# So_do_nguyen_ly.net
KiCad netlist of a schematic drawn in Altium Designer
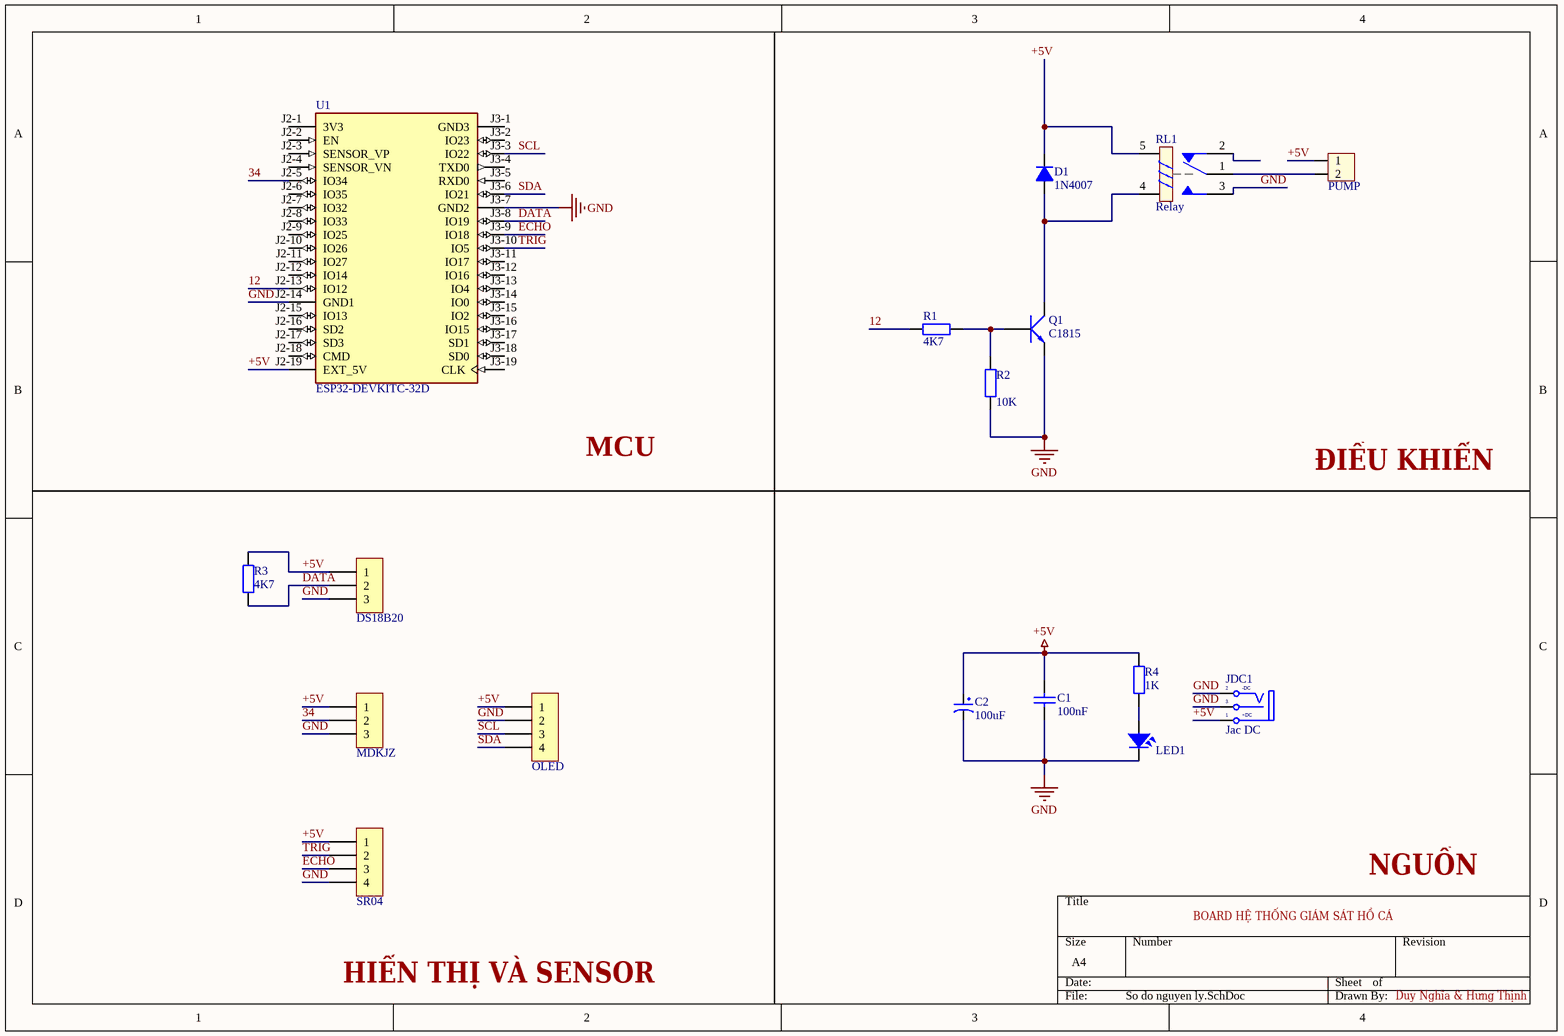
[diagram p0: So do nguyen ly.SchDoc]

(export (version "E")
  (design (tool "Eeschema 10.0.6"))
  (components
    (comp (ref "C1")
      (value "100nF")
      (footprint "tu gom")
      (description "Cắm")
      (libsource (lib "Altium_Lib_by_KhueNguyenCreator") (part "Tu gom 15pF 50V"))
    )
    (comp (ref "C2")
      (value "100uF")
      (footprint "tu hoa 5mm")
      (description "Cắm")
      (libsource (lib "Altium_Lib_by_KhueNguyenCreator") (part "Tu Hoa 100uF 16V 5x7"))
    )
    (comp (ref "D1")
      (value "1N4007")
      (footprint "D1A")
      (description "Diode 1A")
      (libsource (lib "syhaunguyen") (part "D1A"))
    )
    (comp (ref "H1")
      (value "PUMP")
      (footprint "XH2.54M-2")
      (description "Cắm")
      (libsource (lib "Altium_Lib_by_KhueNguyenCreator") (part "Header 2P 2.54 Duc Thang"))
    )
    (comp (ref "H2")
      (value "DS18B20")
      (footprint "Header 3P DC 2.54")
      (description "Cắm")
      (libsource (lib "Altium_Lib_by_KhueNguyenCreator") (part "Header 3P 2.54 Duc Cong"))
    )
    (comp (ref "H3")
      (value "MDKJZ")
      (footprint "Header 3P DC 2.54")
      (description "Cắm")
      (libsource (lib "Altium_Lib_by_KhueNguyenCreator") (part "Header 3P 2.54 Duc Cong"))
    )
    (comp (ref "H4")
      (value "OLED")
      (footprint "XH2.54M-4")
      (description "Cắm")
      (libsource (lib "Altium_Lib_by_KhueNguyenCreator") (part "Header 4P 2.54 Duc Thang"))
    )
    (comp (ref "H5")
      (value "SR04")
      (footprint "XH2.54M-4")
      (description "Cắm")
      (libsource (lib "Altium_Lib_by_KhueNguyenCreator") (part "Header 4P 2.54 Duc Thang"))
    )
    (comp (ref "JDC1")
      (value "Jac DC")
      (footprint "DC-IN")
      (description "Jac DC input")
      (libsource (lib "syhaunguyen") (part "DCIN"))
    )
    (comp (ref "LED1")
      (value "LED")
      (footprint "LED-3")
      (description "LED Single colour Green and Red")
      (libsource (lib "syhaunguyen") (part "LED"))
    )
    (comp (ref "Q1")
      (value "C1815")
      (footprint "TO92")
      (description "NPN transistor")
      (libsource (lib "Altium_Lib_by_KhueNguyenCreator") (part "C1815"))
    )
    (comp (ref "R1")
      (value "4K7")
      (footprint "AXIAL-0.4")
      (description "Resistor")
      (fields (field (name "Comment") "Res2") (field (name "PUBLISHER") "Altium Limited"))
      (libsource (lib "") (part "Res2_1"))
    )
    (comp (ref "R2")
      (value "10K")
      (footprint "AXIAL-0.4")
      (description "Resistor")
      (fields (field (name "Comment") "Res2") (field (name "PUBLISHER") "Altium Limited"))
      (libsource (lib "Miscellaneous Devices") (part "Res2"))
    )
    (comp (ref "R3")
      (value "4K7")
      (footprint "AXIAL-0.4")
      (description "Resistor")
      (fields (field (name "Comment") "Res2") (field (name "PUBLISHER") "Altium Limited"))
      (libsource (lib "Miscellaneous Devices") (part "Res2"))
    )
    (comp (ref "R4")
      (value "1K")
      (footprint "AXIAL-0.4")
      (description "Resistor")
      (fields (field (name "Comment") "Res2") (field (name "PUBLISHER") "Altium Limited"))
      (libsource (lib "Miscellaneous Devices") (part "Res2"))
    )
    (comp (ref "RL1")
      (value "Relay")
      (footprint "RL_SPDT_10A")
      (description "Relay SPDT,10A - 12VDC 5 Pin")
      (libsource (lib "syhaunguyen") (part "Relay 1"))
    )
    (comp (ref "U1")
      (value "ESP32-DEVKITC-32D")
      (footprint "MODULE_ESP32-DEVKITC-32D")
      (description "WiFi Development Tools (802.11) ESP32 General Development Kit, ESP32-WROOM-32D on the board")
      (fields (field (name "MF") "Espressif Systems"))
      (libsource (lib "ESP32-DEVKITC-32D") (part "ESP32-DEVKITC-32D"))
    )
  )
  (nets
    (net (code "1") (name "+5V") (class "Default")
      (node (ref "C1") (pin "1") (pinfunction "1_1") (pintype "passive"))
      (node (ref "C2") (pin "1") (pinfunction "1_1") (pintype "passive"))
      (node (ref "H1") (pin "1") (pinfunction "1_1") (pintype "passive"))
      (node (ref "H2") (pin "1") (pinfunction "1_1") (pintype "passive"))
      (node (ref "H3") (pin "1") (pinfunction "1_1") (pintype "passive"))
      (node (ref "H4") (pin "1") (pinfunction "1_1") (pintype "passive"))
      (node (ref "H5") (pin "1") (pinfunction "1_1") (pintype "passive"))
      (node (ref "JDC1") (pin "1") (pinfunction "T_1") (pintype "passive"))
      (node (ref "R3") (pin "2") (pinfunction "2_2") (pintype "passive"))
      (node (ref "R4") (pin "2") (pinfunction "2_2") (pintype "passive"))
      (node (ref "U1") (pin "J2-19") (pinfunction "EXT_5V_J2-19") (pintype "power_in"))
    )
    (net (code "2") (name "/12") (class "Default")
      (node (ref "R1") (pin "1") (pinfunction "1_1") (pintype "passive"))
      (node (ref "U1") (pin "J2-13") (pinfunction "IO12_J2-13") (pintype "bidirectional"))
    )
    (net (code "3") (name "/34") (class "Default")
      (node (ref "H3") (pin "2") (pinfunction "2_2") (pintype "passive"))
      (node (ref "U1") (pin "J2-5") (pinfunction "IO34_J2-5") (pintype "bidirectional"))
    )
    (net (code "4") (name "/DATA") (class "Default")
      (node (ref "H2") (pin "2") (pinfunction "2_2") (pintype "passive"))
      (node (ref "R3") (pin "1") (pinfunction "1_1") (pintype "passive"))
      (node (ref "U1") (pin "J3-8") (pinfunction "IO19_J3-8") (pintype "bidirectional"))
    )
    (net (code "5") (name "/ECHO") (class "Default")
      (node (ref "H5") (pin "3") (pinfunction "3_3") (pintype "passive"))
      (node (ref "U1") (pin "J3-9") (pinfunction "IO18_J3-9") (pintype "bidirectional"))
    )
    (net (code "6") (name "/SCL") (class "Default")
      (node (ref "H4") (pin "3") (pinfunction "3_3") (pintype "passive"))
      (node (ref "U1") (pin "J3-3") (pinfunction "IO22_J3-3") (pintype "bidirectional"))
    )
    (net (code "7") (name "/SDA") (class "Default")
      (node (ref "H4") (pin "4") (pinfunction "4_4") (pintype "passive"))
      (node (ref "U1") (pin "J3-6") (pinfunction "IO21_J3-6") (pintype "bidirectional"))
    )
    (net (code "8") (name "/TRIG") (class "Default")
      (node (ref "H5") (pin "2") (pinfunction "2_2") (pintype "passive"))
      (node (ref "U1") (pin "J3-10") (pinfunction "IO5_J3-10") (pintype "bidirectional"))
    )
    (net (code "9") (name "GND") (class "Default")
      (node (ref "C1") (pin "2") (pinfunction "2_2") (pintype "passive"))
      (node (ref "C2") (pin "2") (pinfunction "2_2") (pintype "passive"))
      (node (ref "H2") (pin "3") (pinfunction "3_3") (pintype "passive"))
      (node (ref "H3") (pin "3") (pinfunction "3_3") (pintype "passive"))
      (node (ref "H4") (pin "2") (pinfunction "2_2") (pintype "passive"))
      (node (ref "H5") (pin "4") (pinfunction "4_4") (pintype "passive"))
      (node (ref "JDC1") (pin "2") (pinfunction "TN_2") (pintype "passive"))
      (node (ref "JDC1") (pin "3") (pinfunction "S_3") (pintype "power_in"))
      (node (ref "LED1") (pin "2") (pinfunction "2_2") (pintype "passive"))
      (node (ref "Q1") (pin "1") (pinfunction "E_1") (pintype "passive"))
      (node (ref "R2") (pin "1") (pinfunction "1_1") (pintype "passive"))
      (node (ref "RL1") (pin "3") (pinfunction "3_3") (pintype "passive"))
      (node (ref "U1") (pin "J2-14") (pinfunction "GND1_J2-14") (pintype "power_in"))
      (node (ref "U1") (pin "J3-7") (pinfunction "GND2_J3-7") (pintype "power_in"))
    )
    (net (code "10") (name "Net-(D1-A)") (class "Default")
      (node (ref "D1") (pin "1") (pinfunction "A_1") (pintype "passive"))
      (node (ref "Q1") (pin "2") (pinfunction "C_2") (pintype "passive"))
      (node (ref "RL1") (pin "4") (pinfunction "4_4") (pintype "passive"))
    )
    (net (code "11") (name "Net-(D1-K)") (class "Default")
      (node (ref "D1") (pin "2") (pinfunction "K_2") (pintype "passive"))
      (node (ref "RL1") (pin "5") (pinfunction "5_5") (pintype "passive"))
    )
    (net (code "12") (name "Net-(H1-Pad2)") (class "Default")
      (node (ref "H1") (pin "2") (pinfunction "2_2") (pintype "passive"))
      (node (ref "RL1") (pin "1") (pinfunction "1_1") (pintype "passive"))
    )
    (net (code "13") (name "Net-(LED1-Pad1)") (class "Default")
      (node (ref "LED1") (pin "1") (pinfunction "1_1") (pintype "passive"))
      (node (ref "R4") (pin "1") (pinfunction "1_1") (pintype "passive"))
    )
    (net (code "14") (name "Net-(Q1-B)") (class "Default")
      (node (ref "Q1") (pin "3") (pinfunction "B_3") (pintype "passive"))
      (node (ref "R1") (pin "2") (pinfunction "2_2") (pintype "passive"))
      (node (ref "R2") (pin "2") (pinfunction "2_2") (pintype "passive"))
    )
    (net (code "15") (name "unconnected-(RL1-Pad2)") (class "Default")
      (node (ref "RL1") (pin "2") (pinfunction "2_2") (pintype "passive"))
    )
    (net (code "16") (name "unconnected-(U1-3V3-PadJ2-1)") (class "Default")
      (node (ref "U1") (pin "J2-1") (pinfunction "3V3_J2-1") (pintype "power_in"))
    )
    (net (code "17") (name "unconnected-(U1-CLK-PadJ3-19)") (class "Default")
      (node (ref "U1") (pin "J3-19") (pinfunction "CLK_J3-19") (pintype "input"))
    )
    (net (code "18") (name "unconnected-(U1-CMD-PadJ2-18)") (class "Default")
      (node (ref "U1") (pin "J2-18") (pinfunction "CMD_J2-18") (pintype "bidirectional"))
    )
    (net (code "19") (name "unconnected-(U1-EN-PadJ2-2)") (class "Default")
      (node (ref "U1") (pin "J2-2") (pinfunction "EN_J2-2") (pintype "input"))
    )
    (net (code "20") (name "unconnected-(U1-GND3-PadJ3-1)") (class "Default")
      (node (ref "U1") (pin "J3-1") (pinfunction "GND3_J3-1") (pintype "power_in"))
    )
    (net (code "21") (name "unconnected-(U1-IO0-PadJ3-14)") (class "Default")
      (node (ref "U1") (pin "J3-14") (pinfunction "IO0_J3-14") (pintype "bidirectional"))
    )
    (net (code "22") (name "unconnected-(U1-IO2-PadJ3-15)") (class "Default")
      (node (ref "U1") (pin "J3-15") (pinfunction "IO2_J3-15") (pintype "bidirectional"))
    )
    (net (code "23") (name "unconnected-(U1-IO4-PadJ3-13)") (class "Default")
      (node (ref "U1") (pin "J3-13") (pinfunction "IO4_J3-13") (pintype "bidirectional"))
    )
    (net (code "24") (name "unconnected-(U1-IO13-PadJ2-15)") (class "Default")
      (node (ref "U1") (pin "J2-15") (pinfunction "IO13_J2-15") (pintype "bidirectional"))
    )
    (net (code "25") (name "unconnected-(U1-IO14-PadJ2-12)") (class "Default")
      (node (ref "U1") (pin "J2-12") (pinfunction "IO14_J2-12") (pintype "bidirectional"))
    )
    (net (code "26") (name "unconnected-(U1-IO15-PadJ3-16)") (class "Default")
      (node (ref "U1") (pin "J3-16") (pinfunction "IO15_J3-16") (pintype "bidirectional"))
    )
    (net (code "27") (name "unconnected-(U1-IO16-PadJ3-12)") (class "Default")
      (node (ref "U1") (pin "J3-12") (pinfunction "IO16_J3-12") (pintype "bidirectional"))
    )
    (net (code "28") (name "unconnected-(U1-IO17-PadJ3-11)") (class "Default")
      (node (ref "U1") (pin "J3-11") (pinfunction "IO17_J3-11") (pintype "bidirectional"))
    )
    (net (code "29") (name "unconnected-(U1-IO23-PadJ3-2)") (class "Default")
      (node (ref "U1") (pin "J3-2") (pinfunction "IO23_J3-2") (pintype "bidirectional"))
    )
    (net (code "30") (name "unconnected-(U1-IO25-PadJ2-9)") (class "Default")
      (node (ref "U1") (pin "J2-9") (pinfunction "IO25_J2-9") (pintype "bidirectional"))
    )
    (net (code "31") (name "unconnected-(U1-IO26-PadJ2-10)") (class "Default")
      (node (ref "U1") (pin "J2-10") (pinfunction "IO26_J2-10") (pintype "bidirectional"))
    )
    (net (code "32") (name "unconnected-(U1-IO27-PadJ2-11)") (class "Default")
      (node (ref "U1") (pin "J2-11") (pinfunction "IO27_J2-11") (pintype "bidirectional"))
    )
    (net (code "33") (name "unconnected-(U1-IO32-PadJ2-7)") (class "Default")
      (node (ref "U1") (pin "J2-7") (pinfunction "IO32_J2-7") (pintype "bidirectional"))
    )
    (net (code "34") (name "unconnected-(U1-IO33-PadJ2-8)") (class "Default")
      (node (ref "U1") (pin "J2-8") (pinfunction "IO33_J2-8") (pintype "bidirectional"))
    )
    (net (code "35") (name "unconnected-(U1-IO35-PadJ2-6)") (class "Default")
      (node (ref "U1") (pin "J2-6") (pinfunction "IO35_J2-6") (pintype "bidirectional"))
    )
    (net (code "36") (name "unconnected-(U1-RXD0-PadJ3-5)") (class "Default")
      (node (ref "U1") (pin "J3-5") (pinfunction "RXD0_J3-5") (pintype "input"))
    )
    (net (code "37") (name "unconnected-(U1-SD0-PadJ3-18)") (class "Default")
      (node (ref "U1") (pin "J3-18") (pinfunction "SD0_J3-18") (pintype "bidirectional"))
    )
    (net (code "38") (name "unconnected-(U1-SD1-PadJ3-17)") (class "Default")
      (node (ref "U1") (pin "J3-17") (pinfunction "SD1_J3-17") (pintype "bidirectional"))
    )
    (net (code "39") (name "unconnected-(U1-SD2-PadJ2-16)") (class "Default")
      (node (ref "U1") (pin "J2-16") (pinfunction "SD2_J2-16") (pintype "bidirectional"))
    )
    (net (code "40") (name "unconnected-(U1-SD3-PadJ2-17)") (class "Default")
      (node (ref "U1") (pin "J2-17") (pinfunction "SD3_J2-17") (pintype "bidirectional"))
    )
    (net (code "41") (name "unconnected-(U1-SENSOR_VN-PadJ2-4)") (class "Default")
      (node (ref "U1") (pin "J2-4") (pinfunction "SENSOR_VN_J2-4") (pintype "input"))
    )
    (net (code "42") (name "unconnected-(U1-SENSOR_VP-PadJ2-3)") (class "Default")
      (node (ref "U1") (pin "J2-3") (pinfunction "SENSOR_VP_J2-3") (pintype "input"))
    )
    (net (code "43") (name "unconnected-(U1-TXD0-PadJ3-4)") (class "Default")
      (node (ref "U1") (pin "J3-4") (pinfunction "TXD0_J3-4") (pintype "output"))
    )
  )
)
